# Mini_AHRS.net
KiCad netlist of a schematic drawn in Altium Designer
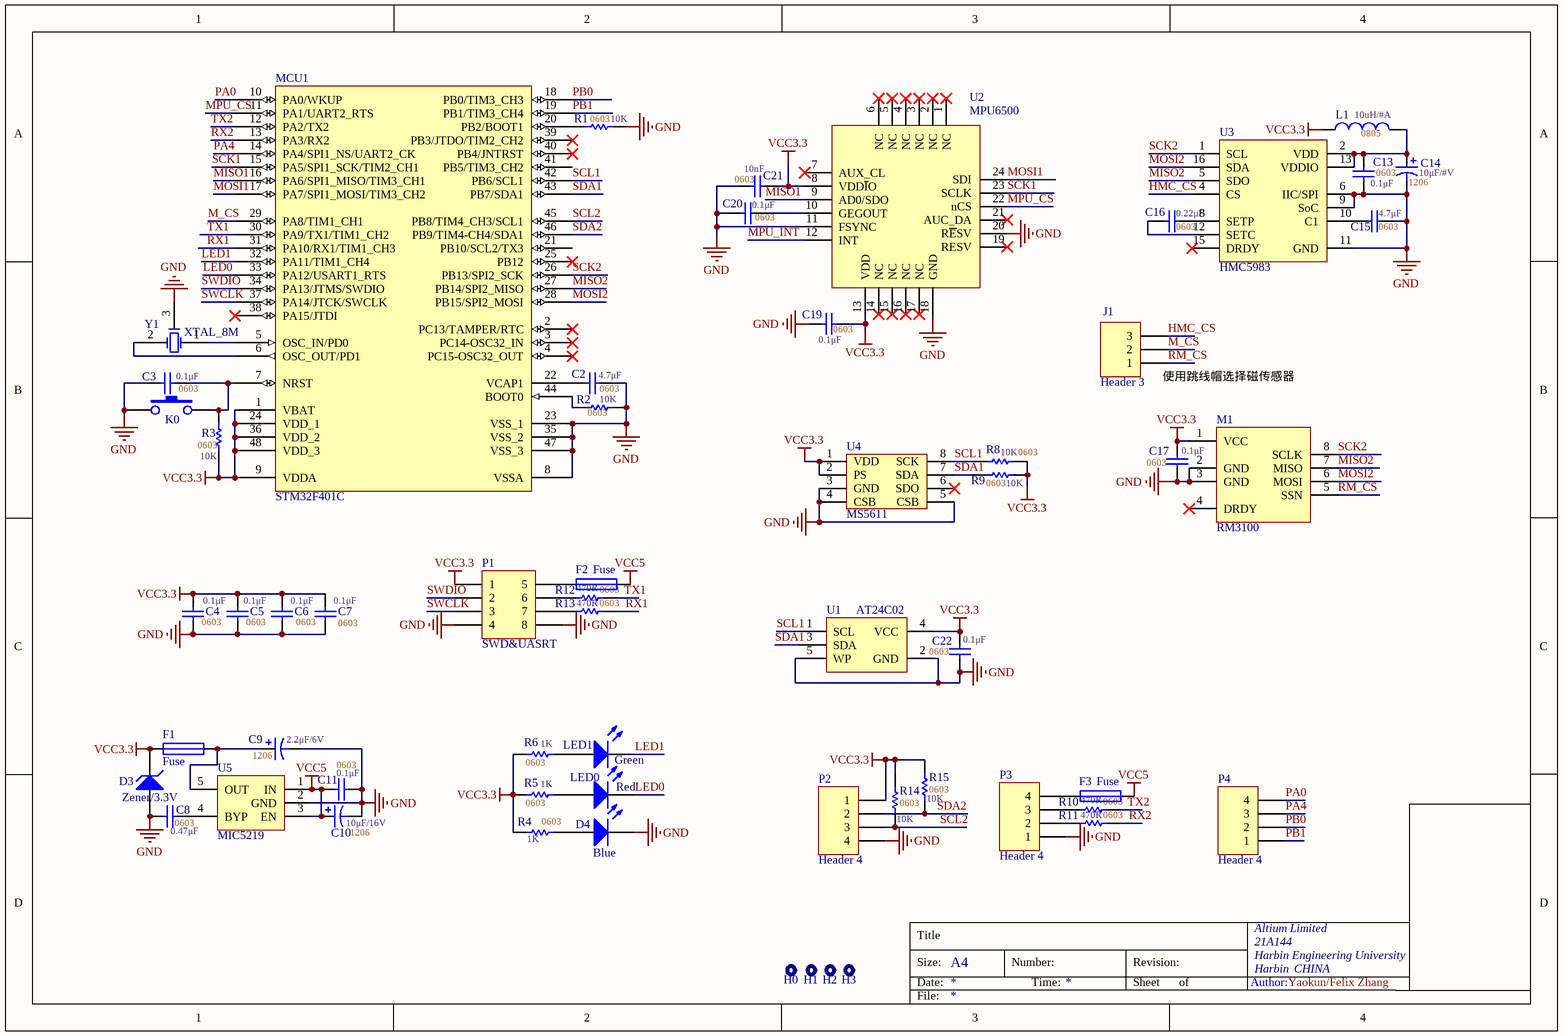
[diagram p0: Mini_AHRS.SchDoc]

(export (version "E")
  (design (tool "Eeschema 10.0.6"))
  (components
    (comp (ref "C2")
      (value "4.7μF")
      (footprint "CAP_0603_16*08")
      (description "Capacitor")
      (fields
        (field (name "PACKAGEREFERENCE") "0603")
        (field (name "Comment") "0603")
        (field (name "PUBLISHER") "Altium Limited")
      )
      (libsource (lib "Belong_to_Kongkong") (part "Cap"))
    )
    (comp (ref "C3")
      (value "0.1μF")
      (footprint "CAP_0603_16*08")
      (description "Capacitor")
      (fields
        (field (name "PACKAGEREFERENCE") "0603")
        (field (name "Comment") "0603")
        (field (name "PUBLISHER") "Altium Limited")
      )
      (libsource (lib "Belong_to_Kongkong") (part "Cap"))
    )
    (comp (ref "C4")
      (value "0.1μF")
      (footprint "CAP_0603_16*08")
      (description "Capacitor")
      (fields
        (field (name "PACKAGEREFERENCE") "0603")
        (field (name "Comment") "0603")
        (field (name "PUBLISHER") "Altium Limited")
      )
      (libsource (lib "Belong_to_Kongkong") (part "Cap"))
    )
    (comp (ref "C5")
      (value "0.1μF")
      (footprint "CAP_0603_16*08")
      (description "Capacitor")
      (fields
        (field (name "PACKAGEREFERENCE") "0603")
        (field (name "Comment") "0603")
        (field (name "PUBLISHER") "Altium Limited")
      )
      (libsource (lib "Belong_to_Kongkong") (part "Cap"))
    )
    (comp (ref "C6")
      (value "0.1μF")
      (footprint "CAP_0603_16*08")
      (description "Capacitor")
      (fields
        (field (name "PACKAGEREFERENCE") "0603")
        (field (name "Comment") "0603")
        (field (name "PUBLISHER") "Altium Limited")
      )
      (libsource (lib "Belong_to_Kongkong") (part "Cap"))
    )
    (comp (ref "C7")
      (value "0.1μF")
      (footprint "CAP_0603_16*08")
      (description "Capacitor")
      (fields
        (field (name "PACKAGEREFERENCE") "0603")
        (field (name "Comment") "0603")
        (field (name "PUBLISHER") "Altium Limited")
      )
      (libsource (lib "Belong_to_Kongkong") (part "Cap"))
    )
    (comp (ref "C8")
      (value "0.47μF")
      (footprint "CAP_0603_16*08")
      (description "Capacitor")
      (fields
        (field (name "PACKAGEREFERENCE") "0603")
        (field (name "Comment") "0603")
        (field (name "PUBLISHER") "Altium Limited")
      )
      (libsource (lib "Belong_to_Kongkong") (part "Cap"))
    )
    (comp (ref "C9")
      (value "2.2μF/6V")
      (footprint "CAP_0805_20*12")
      (description "Polarized Capacitor (Axial)")
      (fields
        (field (name "PACKAGEREFERENCE") "1206")
        (field (name "Comment") "Polar")
        (field (name "PUBLISHER") "Altium Limited")
      )
      (libsource (lib "Belong_to_Kongkong") (part "Cap Pol"))
    )
    (comp (ref "C10")
      (value "10μF/16V")
      (footprint "CAP_1206")
      (description "Polarized Capacitor (Axial)")
      (fields
        (field (name "PACKAGEREFERENCE") "1206")
        (field (name "Comment") "Polar")
        (field (name "PUBLISHER") "Altium Limited")
      )
      (libsource (lib "Belong_to_Kongkong") (part "Cap Pol"))
    )
    (comp (ref "C11")
      (value "0.1μF")
      (footprint "CAP_0603_16*08")
      (description "Capacitor")
      (fields
        (field (name "PACKAGEREFERENCE") "0603")
        (field (name "Comment") "0603")
        (field (name "PUBLISHER") "Altium Limited")
      )
      (libsource (lib "Belong_to_Kongkong") (part "Cap"))
    )
    (comp (ref "C13")
      (value "0.1μF")
      (footprint "CAP_0603_16*08")
      (description "Capacitor")
      (fields
        (field (name "PACKAGEREFERENCE") "0603")
        (field (name "Comment") "0603")
        (field (name "PUBLISHER") "Altium Limited")
      )
      (libsource (lib "Belong_to_Kongkong") (part "Cap"))
    )
    (comp (ref "C14")
      (value "10μF/#V")
      (footprint "CAP_0805_20*12")
      (description "Polarized Capacitor (Axial)")
      (fields
        (field (name "PACKAGEREFERENCE") "1206")
        (field (name "Comment") "Polar")
        (field (name "PUBLISHER") "Altium Limited")
      )
      (libsource (lib "Belong_to_Kongkong") (part "Cap Pol"))
    )
    (comp (ref "C15")
      (value "4.7μF")
      (footprint "CAP_0805_20*12")
      (description "Capacitor")
      (fields
        (field (name "PACKAGEREFERENCE") "0603")
        (field (name "Comment") "0603")
        (field (name "PUBLISHER") "Altium Limited")
      )
      (libsource (lib "Belong_to_Kongkong") (part "Cap"))
    )
    (comp (ref "C16")
      (value "0.22μF")
      (footprint "CAP_0603_16*08")
      (description "Capacitor")
      (fields
        (field (name "PACKAGEREFERENCE") "0603")
        (field (name "Comment") "0603")
        (field (name "PUBLISHER") "Altium Limited")
      )
      (libsource (lib "Belong_to_Kongkong") (part "Cap"))
    )
    (comp (ref "C17")
      (value "0.1μF")
      (footprint "CAP_0603_16*08")
      (description "Capacitor")
      (fields
        (field (name "PACKAGEREFERENCE") "0603")
        (field (name "Comment") "0603")
        (field (name "PUBLISHER") "Altium Limited")
      )
      (libsource (lib "Belong_to_Kongkong") (part "Cap"))
    )
    (comp (ref "C19")
      (value "0.1μF")
      (footprint "CAP_0603_16*08")
      (description "Capacitor")
      (fields
        (field (name "PACKAGEREFERENCE") "0603")
        (field (name "Comment") "0603")
        (field (name "PUBLISHER") "Altium Limited")
      )
      (libsource (lib "Belong_to_Kongkong") (part "Cap"))
    )
    (comp (ref "C20")
      (value "0.1μF")
      (footprint "CAP_0603_16*08")
      (description "Capacitor")
      (fields
        (field (name "PACKAGEREFERENCE") "0603")
        (field (name "Comment") "0603")
        (field (name "PUBLISHER") "Altium Limited")
      )
      (libsource (lib "Belong_to_Kongkong") (part "Cap"))
    )
    (comp (ref "C21")
      (value "10nF")
      (footprint "CAP_0603_16*08")
      (description "Capacitor")
      (fields
        (field (name "PACKAGEREFERENCE") "0603")
        (field (name "Comment") "0603")
        (field (name "PUBLISHER") "Altium Limited")
      )
      (libsource (lib "Belong_to_Kongkong") (part "Cap"))
    )
    (comp (ref "C22")
      (value "0.1μF")
      (footprint "CAP_0603_16*08")
      (description "Capacitor")
      (fields
        (field (name "PACKAGEREFERENCE") "0603")
        (field (name "Comment") "0603")
        (field (name "PUBLISHER") "Altium Limited")
      )
      (libsource (lib "Belong_to_Kongkong") (part "Cap"))
    )
    (comp (ref "D3")
      (value "Zener/3.3V")
      (footprint "SOD523")
      (description "Zener Diode")
      (fields (field (name "PUBLISHER") "Altium Limited"))
      (libsource (lib "Belong_to_Kongkong") (part "D Zener"))
    )
    (comp (ref "D4")
      (value "Blue")
      (footprint "CAP_0603_16*08")
      (description "Typical RED, GREEN, YELLOW, AMBER GaAs LED")
      (fields (field (name "PUBLISHER") "Altium Limited"))
      (libsource (lib "Belong_to_Kongkong") (part "LED"))
    )
    (comp (ref "F1")
      (value "Fuse")
      (footprint "RES_0805_20*12")
      (fields (field (name "PUBLISHER") "Altium Limited"))
      (libsource (lib "Belong_to_Kongkong") (part "Fuse 1"))
    )
    (comp (ref "F2")
      (value "Fuse")
      (footprint "RES_0805_20*12")
      (fields (field (name "PUBLISHER") "Altium Limited"))
      (libsource (lib "Belong_to_Kongkong") (part "Fuse 1"))
    )
    (comp (ref "F3")
      (value "Fuse")
      (footprint "RES_0805_20*12")
      (fields (field (name "PUBLISHER") "Altium Limited"))
      (libsource (lib "Belong_to_Kongkong") (part "Fuse 1"))
    )
    (comp (ref "H0")
      (value "Pad-SCREW")
      (footprint "PAD_M2")
      (libsource (lib "Belong_to_Kongkong") (part "Pad-SCREW"))
    )
    (comp (ref "H1")
      (value "Pad-SCREW")
      (footprint "PAD_M2")
      (libsource (lib "Belong_to_Kongkong") (part "Pad-SCREW"))
    )
    (comp (ref "H2")
      (value "Pad-SCREW")
      (footprint "PAD_M2")
      (libsource (lib "Belong_to_Kongkong") (part "Pad-SCREW"))
    )
    (comp (ref "H3")
      (value "Pad-SCREW")
      (footprint "PAD_M2")
      (libsource (lib "Belong_to_Kongkong") (part "Pad-SCREW"))
    )
    (comp (ref "J1")
      (value "Header 3")
      (footprint "HEADER1*3sig")
      (description "Header, 3-Pin")
      (fields (field (name "PUBLISHER") "Altium Limited"))
      (libsource (lib "Belong_to_Kongkong") (part "Header 3"))
    )
    (comp (ref "K0") (value "KEY") (footprint "KEY_2") (libsource (lib "Belong_to_Kongkong") (part "KEY")))
    (comp (ref "L1")
      (value "10uH/#A")
      (footprint "IND_0805_20*12")
      (description "Inductor")
      (fields
        (field (name "PACKAGEREFERENCE") "0805")
        (field (name "Comment") "MODEL?")
        (field (name "PUBLISHER") "Altium Limited")
      )
      (libsource (lib "Belong_to_Kongkong") (part "Inductor"))
    )
    (comp (ref "LED0")
      (value "Red")
      (footprint "CAP_0603_16*08")
      (description "Typical RED, GREEN, YELLOW, AMBER GaAs LED")
      (fields (field (name "PUBLISHER") "Altium Limited"))
      (libsource (lib "Belong_to_Kongkong") (part "LED"))
    )
    (comp (ref "LED1")
      (value "Green")
      (footprint "CAP_0603_16*08")
      (description "Typical RED, GREEN, YELLOW, AMBER GaAs LED")
      (fields (field (name "PUBLISHER") "Altium Limited"))
      (libsource (lib "Belong_to_Kongkong") (part "LED"))
    )
    (comp (ref "M1")
      (value "RM3100")
      (footprint "RM3100_MODEUL")
      (libsource (lib "Belong_to_Kongkong") (part "RM3100_MODEUL"))
    )
    (comp (ref "MCU1")
      (value "STM32F401C")
      (footprint "QFN-48_7x7x05P")
      (libsource (lib "Belong_to_Kongkong") (part "STM32F401C*U6"))
    )
    (comp (ref "P1")
      (value "SWD&UASRT")
      (footprint "HEADER2*4_PIN")
      (description "Header, 4-Pin, Dual row")
      (fields (field (name "PUBLISHER") "Altium Limited"))
      (libsource (lib "Belong_to_Kongkong") (part "Header 4X2"))
    )
    (comp (ref "P2")
      (value "Header 4")
      (footprint "JST_CH1.0_4P")
      (description "Header, 4-Pin")
      (fields (field (name "PUBLISHER") "Altium Limited"))
      (libsource (lib "") (part "Header 4_1"))
    )
    (comp (ref "P3")
      (value "Header 4")
      (footprint "JST_CH1.0_4P")
      (description "Header, 4-Pin")
      (fields (field (name "PUBLISHER") "Altium Limited"))
      (libsource (lib "Belong_to_Kongkong") (part "Header 4"))
    )
    (comp (ref "P4")
      (value "Header 4")
      (footprint "HEADER1*4_PIN")
      (description "Header, 4-Pin")
      (fields (field (name "PUBLISHER") "Altium Limited"))
      (libsource (lib "Belong_to_Kongkong") (part "Header 4"))
    )
    (comp (ref "R1")
      (value "10K")
      (footprint "RES_0603_16*08")
      (description "Resistor")
      (fields
        (field (name "PACKAGEREFERENCE") "0603")
        (field (name "Comment") "SMD")
        (field (name "PUBLISHER") "Altium Limited")
      )
      (libsource (lib "Belong_to_Kongkong") (part "RES_SMD"))
    )
    (comp (ref "R2")
      (value "10K")
      (footprint "RES_0603_16*08")
      (description "Resistor")
      (fields
        (field (name "PACKAGEREFERENCE") "0603")
        (field (name "Comment") "SMD")
        (field (name "PUBLISHER") "Altium Limited")
      )
      (libsource (lib "Belong_to_Kongkong") (part "RES_SMD"))
    )
    (comp (ref "R3")
      (value "10K")
      (footprint "RES_0603_16*08")
      (description "Resistor")
      (fields
        (field (name "PACKAGEREFERENCE") "0603")
        (field (name "Comment") "SMD")
        (field (name "PUBLISHER") "Altium Limited")
      )
      (libsource (lib "Belong_to_Kongkong") (part "RES_SMD"))
    )
    (comp (ref "R4")
      (value "1K")
      (footprint "RES_0603_16*08")
      (description "Resistor")
      (fields
        (field (name "PACKAGEREFERENCE") "0603")
        (field (name "Comment") "SMD")
        (field (name "PUBLISHER") "Altium Limited")
      )
      (libsource (lib "Belong_to_Kongkong") (part "RES_SMD"))
    )
    (comp (ref "R5")
      (value "1K")
      (footprint "RES_0603_16*08")
      (description "Resistor")
      (fields
        (field (name "PACKAGEREFERENCE") "0603")
        (field (name "Comment") "SMD")
        (field (name "PUBLISHER") "Altium Limited")
      )
      (libsource (lib "Belong_to_Kongkong") (part "RES_SMD"))
    )
    (comp (ref "R6")
      (value "1K")
      (footprint "RES_0603_16*08")
      (description "Resistor")
      (fields
        (field (name "PACKAGEREFERENCE") "0603")
        (field (name "Comment") "SMD")
        (field (name "PUBLISHER") "Altium Limited")
      )
      (libsource (lib "Belong_to_Kongkong") (part "RES_SMD"))
    )
    (comp (ref "R8")
      (value "10K")
      (footprint "RES_0603_16*08")
      (description "Resistor")
      (fields
        (field (name "PACKAGEREFERENCE") "0603")
        (field (name "Comment") "SMD")
        (field (name "PUBLISHER") "Altium Limited")
      )
      (libsource (lib "Belong_to_Kongkong") (part "RES_SMD"))
    )
    (comp (ref "R9")
      (value "10K")
      (footprint "RES_0603_16*08")
      (description "Resistor")
      (fields
        (field (name "PACKAGEREFERENCE") "0603")
        (field (name "Comment") "SMD")
        (field (name "PUBLISHER") "Altium Limited")
      )
      (libsource (lib "Belong_to_Kongkong") (part "RES_SMD"))
    )
    (comp (ref "R10")
      (value "470R")
      (footprint "RES_0603_16*08")
      (description "Resistor")
      (fields
        (field (name "PACKAGEREFERENCE") "0603")
        (field (name "Comment") "SMD")
        (field (name "PUBLISHER") "Altium Limited")
      )
      (libsource (lib "Belong_to_Kongkong") (part "RES_SMD"))
    )
    (comp (ref "R11")
      (value "470R")
      (footprint "RES_0603_16*08")
      (description "Resistor")
      (fields
        (field (name "PACKAGEREFERENCE") "0603")
        (field (name "Comment") "SMD")
        (field (name "PUBLISHER") "Altium Limited")
      )
      (libsource (lib "Belong_to_Kongkong") (part "RES_SMD"))
    )
    (comp (ref "R12")
      (value "470R")
      (footprint "RES_0603_16*08")
      (description "Resistor")
      (fields
        (field (name "PACKAGEREFERENCE") "0603")
        (field (name "Comment") "SMD")
        (field (name "PUBLISHER") "Altium Limited")
      )
      (libsource (lib "Belong_to_Kongkong") (part "RES_SMD"))
    )
    (comp (ref "R13")
      (value "470R")
      (footprint "RES_0603_16*08")
      (description "Resistor")
      (fields
        (field (name "PACKAGEREFERENCE") "0603")
        (field (name "Comment") "SMD")
        (field (name "PUBLISHER") "Altium Limited")
      )
      (libsource (lib "Belong_to_Kongkong") (part "RES_SMD"))
    )
    (comp (ref "R14")
      (value "10K")
      (footprint "RES_0603_16*08")
      (description "Resistor")
      (fields
        (field (name "PACKAGEREFERENCE") "0603")
        (field (name "Comment") "SMD")
        (field (name "PUBLISHER") "Altium Limited")
      )
      (libsource (lib "Belong_to_Kongkong") (part "RES_SMD"))
    )
    (comp (ref "R15")
      (value "10K")
      (footprint "RES_0603_16*08")
      (description "Resistor")
      (fields
        (field (name "PACKAGEREFERENCE") "0603")
        (field (name "Comment") "SMD")
        (field (name "PUBLISHER") "Altium Limited")
      )
      (libsource (lib "Belong_to_Kongkong") (part "RES_SMD"))
    )
    (comp (ref "U1")
      (value "AT24C02")
      (footprint "SOT23-5")
      (libsource (lib "Belong_to_Kongkong") (part "AT24C02-5Pin"))
    )
    (comp (ref "U2")
      (value "MPU6500")
      (footprint "QFN24_3*3*0.4")
      (libsource (lib "Belong_to_Kongkong") (part "MPU6500"))
    )
    (comp (ref "U3")
      (value "HMC5983")
      (footprint "QFN-16_3x3x05P")
      (libsource (lib "Belong_to_Kongkong") (part "HMC5983"))
    )
    (comp (ref "U4")
      (value "MS5611")
      (footprint "MS5611")
      (libsource (lib "Belong_to_Kongkong") (part "MS5611"))
    )
    (comp (ref "U5")
      (value "MIC5219")
      (footprint "SOT23-5")
      (libsource (lib "Belong_to_Kongkong") (part "MIC5219"))
    )
    (comp (ref "Y1")
      (value "XTAL_8M")
      (footprint "XTAL_SMD_8M")
      (libsource (lib "Belong_to_Kongkong") (part "XTAL_8M"))
    )
  )
  (nets
    (net (code "1") (name "/HMC_CS") (class "Default")
      (node (ref "J1") (pin "3") (pinfunction "3_3") (pintype "passive"))
      (node (ref "U3") (pin "4") (pinfunction "CS_4") (pintype "passive"))
    )
    (net (code "2") (name "/LED0") (class "Default")
      (node (ref "LED0") (pin "2") (pinfunction "K_2") (pintype "passive"))
      (node (ref "MCU1") (pin "33") (pinfunction "PA12/USART1_RTS_33") (pintype "bidirectional"))
    )
    (net (code "3") (name "/LED1") (class "Default")
      (node (ref "LED1") (pin "2") (pinfunction "K_2") (pintype "passive"))
      (node (ref "MCU1") (pin "32") (pinfunction "PA11/TIM1_CH4_32") (pintype "bidirectional"))
    )
    (net (code "4") (name "/MISO1") (class "Default")
      (node (ref "MCU1") (pin "16") (pinfunction "PA6/SPI1_MISO/TIM3_CH1_16") (pintype "bidirectional"))
      (node (ref "U2") (pin "9") (pinfunction "AD0/SDO_9") (pintype "open_collector"))
    )
    (net (code "5") (name "/MISO2") (class "Default")
      (node (ref "M1") (pin "7") (pinfunction "MISO_7") (pintype "power_in"))
      (node (ref "MCU1") (pin "27") (pinfunction "PB14/SPI2_MISO_27") (pintype "bidirectional"))
      (node (ref "U3") (pin "5") (pinfunction "SDO_5") (pintype "passive"))
    )
    (net (code "6") (name "/MOSI1") (class "Default")
      (node (ref "MCU1") (pin "17") (pinfunction "PA7/SPI1_MOSI/TIM3_CH2_17") (pintype "bidirectional"))
      (node (ref "U2") (pin "24") (pinfunction "SDI_24") (pintype "open_collector"))
    )
    (net (code "7") (name "/MOSI2") (class "Default")
      (node (ref "M1") (pin "6") (pinfunction "MOSI_6") (pintype "power_in"))
      (node (ref "MCU1") (pin "28") (pinfunction "PB15/SPI2_MOSI_28") (pintype "bidirectional"))
      (node (ref "U3") (pin "16") (pinfunction "SDA_16") (pintype "passive"))
    )
    (net (code "8") (name "/MPU_CS") (class "Default")
      (node (ref "MCU1") (pin "11") (pinfunction "PA1/UART2_RTS_11") (pintype "bidirectional"))
      (node (ref "U2") (pin "22") (pinfunction "nCS_22") (pintype "open_collector"))
    )
    (net (code "9") (name "/MPU_INT") (class "Default")
      (node (ref "U2") (pin "12") (pinfunction "INT_12") (pintype "open_collector"))
    )
    (net (code "10") (name "/M_CS") (class "Default")
      (node (ref "J1") (pin "2") (pinfunction "2_2") (pintype "passive"))
      (node (ref "MCU1") (pin "29") (pinfunction "PA8/TIM1_CH1_29") (pintype "bidirectional"))
    )
    (net (code "11") (name "/PA0") (class "Default")
      (node (ref "MCU1") (pin "10") (pinfunction "PA0/WKUP_10") (pintype "bidirectional"))
      (node (ref "P4") (pin "4") (pinfunction "4_4") (pintype "passive"))
    )
    (net (code "12") (name "/PA4") (class "Default")
      (node (ref "MCU1") (pin "14") (pinfunction "PA4/SPI1_NS/UART2_CK_14") (pintype "bidirectional"))
      (node (ref "P4") (pin "3") (pinfunction "3_3") (pintype "passive"))
    )
    (net (code "13") (name "/PB0") (class "Default")
      (node (ref "MCU1") (pin "18") (pinfunction "PB0/TIM3_CH3_18") (pintype "bidirectional"))
      (node (ref "P4") (pin "2") (pinfunction "2_2") (pintype "passive"))
    )
    (net (code "14") (name "/PB1") (class "Default")
      (node (ref "MCU1") (pin "19") (pinfunction "PB1/TIM3_CH4_19") (pintype "bidirectional"))
      (node (ref "P4") (pin "1") (pinfunction "1_1") (pintype "passive"))
    )
    (net (code "15") (name "/RM_CS") (class "Default")
      (node (ref "J1") (pin "1") (pinfunction "1_1") (pintype "passive"))
      (node (ref "M1") (pin "5") (pinfunction "SSN_5") (pintype "power_in"))
    )
    (net (code "16") (name "/RX1") (class "Default")
      (node (ref "MCU1") (pin "31") (pinfunction "PA10/RX1/TIM1_CH3_31") (pintype "bidirectional"))
      (node (ref "R13") (pin "1") (pinfunction "1_1") (pintype "passive"))
    )
    (net (code "17") (name "/RX2") (class "Default")
      (node (ref "MCU1") (pin "13") (pinfunction "PA3/RX2_13") (pintype "bidirectional"))
      (node (ref "R11") (pin "1") (pinfunction "1_1") (pintype "passive"))
    )
    (net (code "18") (name "/SCK1") (class "Default")
      (node (ref "MCU1") (pin "15") (pinfunction "PA5/SPI1_SCK/TIM2_CH1_15") (pintype "bidirectional"))
      (node (ref "U2") (pin "23") (pinfunction "SCLK_23") (pintype "open_collector"))
    )
    (net (code "19") (name "/SCK2") (class "Default")
      (node (ref "M1") (pin "8") (pinfunction "SCLK_8") (pintype "power_in"))
      (node (ref "MCU1") (pin "26") (pinfunction "PB13/SPI2_SCK_26") (pintype "bidirectional"))
      (node (ref "U3") (pin "1") (pinfunction "SCL_1") (pintype "passive"))
    )
    (net (code "20") (name "/SCL1") (class "Default")
      (node (ref "MCU1") (pin "42") (pinfunction "PB6/SCL1_42") (pintype "bidirectional"))
      (node (ref "R8") (pin "1") (pinfunction "1_1") (pintype "passive"))
      (node (ref "U1") (pin "1") (pinfunction "SCL_1") (pintype "passive"))
      (node (ref "U4") (pin "8") (pinfunction "SCK_8") (pintype "open_collector"))
    )
    (net (code "21") (name "/SCL2") (class "Default")
      (node (ref "MCU1") (pin "45") (pinfunction "PB8/TIM4_CH3/SCL1_45") (pintype "bidirectional"))
      (node (ref "P2") (pin "3") (pinfunction "3_3") (pintype "passive"))
      (node (ref "R14") (pin "2") (pinfunction "2_2") (pintype "passive"))
    )
    (net (code "22") (name "/SDA1") (class "Default")
      (node (ref "MCU1") (pin "43") (pinfunction "PB7/SDA1_43") (pintype "bidirectional"))
      (node (ref "R9") (pin "1") (pinfunction "1_1") (pintype "passive"))
      (node (ref "U1") (pin "3") (pinfunction "SDA_3") (pintype "passive"))
      (node (ref "U4") (pin "7") (pinfunction "SDA_7") (pintype "open_collector"))
    )
    (net (code "23") (name "/SDA2") (class "Default")
      (node (ref "MCU1") (pin "46") (pinfunction "PB9/TIM4-CH4/SDA1_46") (pintype "bidirectional"))
      (node (ref "P2") (pin "2") (pinfunction "2_2") (pintype "passive"))
      (node (ref "R15") (pin "2") (pinfunction "2_2") (pintype "passive"))
    )
    (net (code "24") (name "/SWCLK") (class "Default")
      (node (ref "MCU1") (pin "37") (pinfunction "PA14/JTCK/SWCLK_37") (pintype "bidirectional"))
      (node (ref "P1") (pin "3") (pinfunction "3_3") (pintype "passive"))
    )
    (net (code "25") (name "/SWDIO") (class "Default")
      (node (ref "MCU1") (pin "34") (pinfunction "PA13/JTMS/SWDIO_34") (pintype "bidirectional"))
      (node (ref "P1") (pin "2") (pinfunction "2_2") (pintype "passive"))
    )
    (net (code "26") (name "/TX1") (class "Default")
      (node (ref "MCU1") (pin "30") (pinfunction "PA9/TX1/TIM1_CH2_30") (pintype "bidirectional"))
      (node (ref "R12") (pin "1") (pinfunction "1_1") (pintype "passive"))
    )
    (net (code "27") (name "/TX2") (class "Default")
      (node (ref "MCU1") (pin "12") (pinfunction "PA2/TX2_12") (pintype "bidirectional"))
      (node (ref "R10") (pin "1") (pinfunction "1_1") (pintype "passive"))
    )
    (net (code "28") (name "GND") (class "Default")
      (node (ref "C10") (pin "2") (pinfunction "2_2") (pintype "passive"))
      (node (ref "C11") (pin "1") (pinfunction "1_1") (pintype "passive"))
      (node (ref "C13") (pin "2") (pinfunction "2_2") (pintype "passive"))
      (node (ref "C14") (pin "2") (pinfunction "2_2") (pintype "passive"))
      (node (ref "C15") (pin "1") (pinfunction "1_1") (pintype "passive"))
      (node (ref "C17") (pin "2") (pinfunction "2_2") (pintype "passive"))
      (node (ref "C19") (pin "2") (pinfunction "2_2") (pintype "passive"))
      (node (ref "C2") (pin "1") (pinfunction "1_1") (pintype "passive"))
      (node (ref "C20") (pin "2") (pinfunction "2_2") (pintype "passive"))
      (node (ref "C21") (pin "2") (pinfunction "2_2") (pintype "passive"))
      (node (ref "C22") (pin "2") (pinfunction "2_2") (pintype "passive"))
      (node (ref "C3") (pin "1") (pinfunction "1_1") (pintype "passive"))
      (node (ref "C4") (pin "2") (pinfunction "2_2") (pintype "passive"))
      (node (ref "C5") (pin "2") (pinfunction "2_2") (pintype "passive"))
      (node (ref "C6") (pin "2") (pinfunction "2_2") (pintype "passive"))
      (node (ref "C7") (pin "1") (pinfunction "1_1") (pintype "passive"))
      (node (ref "C8") (pin "2") (pinfunction "2_2") (pintype "passive"))
      (node (ref "C9") (pin "2") (pinfunction "2_2") (pintype "passive"))
      (node (ref "D3") (pin "1") (pinfunction "A_1") (pintype "passive"))
      (node (ref "D4") (pin "2") (pinfunction "K_2") (pintype "passive"))
      (node (ref "K0") (pin "1") (pinfunction "1_1") (pintype "passive"))
      (node (ref "M1") (pin "2") (pinfunction "GND_2") (pintype "power_in"))
      (node (ref "M1") (pin "3") (pinfunction "GND_3") (pintype "power_in"))
      (node (ref "MCU1") (pin "23") (pinfunction "VSS_1_23") (pintype "power_in"))
      (node (ref "MCU1") (pin "35") (pinfunction "VSS_2_35") (pintype "power_in"))
      (node (ref "MCU1") (pin "47") (pinfunction "VSS_3_47") (pintype "power_in"))
      (node (ref "MCU1") (pin "8") (pinfunction "VSSA_8") (pintype "power_in"))
      (node (ref "P1") (pin "4") (pinfunction "4_4") (pintype "passive"))
      (node (ref "P1") (pin "8") (pinfunction "8_8") (pintype "passive"))
      (node (ref "P2") (pin "4") (pinfunction "4_4") (pintype "passive"))
      (node (ref "P3") (pin "1") (pinfunction "1_1") (pintype "passive"))
      (node (ref "R1") (pin "2") (pinfunction "2_2") (pintype "passive"))
      (node (ref "R2") (pin "1") (pinfunction "1_1") (pintype "passive"))
      (node (ref "U1") (pin "2") (pinfunction "GND_2") (pintype "passive"))
      (node (ref "U1") (pin "5") (pinfunction "WP_5") (pintype "passive"))
      (node (ref "U2") (pin "11") (pinfunction "FSYNC_11") (pintype "open_collector"))
      (node (ref "U2") (pin "18") (pinfunction "GND_18") (pintype "open_collector"))
      (node (ref "U2") (pin "20") (pinfunction "R~{E}SV_20") (pintype "open_collector"))
      (node (ref "U3") (pin "11") (pinfunction "GND_11") (pintype "power_in"))
      (node (ref "U3") (pin "6") (pinfunction "IIC/SPI_6") (pintype "passive"))
      (node (ref "U3") (pin "9") (pinfunction "SoC_9") (pintype "passive"))
      (node (ref "U4") (pin "3") (pinfunction "GND_3") (pintype "open_collector"))
      (node (ref "U4") (pin "4") (pinfunction "CSB_4") (pintype "open_collector"))
      (node (ref "U4") (pin "5") (pinfunction "CSB_5") (pintype "open_collector"))
      (node (ref "U5") (pin "2") (pinfunction "GND_2") (pintype "passive"))
      (node (ref "Y1") (pin "3") (pinfunction "OSC3_3") (pintype "passive"))
    )
    (net (code "29") (name "Net-(D4-A)") (class "Default")
      (node (ref "D4") (pin "1") (pinfunction "A_1") (pintype "passive"))
      (node (ref "R4") (pin "2") (pinfunction "2_2") (pintype "passive"))
    )
    (net (code "30") (name "Net-(F2-Pad1)") (class "Default")
      (node (ref "F2") (pin "1") (pinfunction "1_1") (pintype "passive"))
      (node (ref "P1") (pin "5") (pinfunction "5_5") (pintype "passive"))
    )
    (net (code "31") (name "Net-(F3-Pad1)") (class "Default")
      (node (ref "F3") (pin "1") (pinfunction "1_1") (pintype "passive"))
      (node (ref "P3") (pin "4") (pinfunction "4_4") (pintype "passive"))
    )
    (net (code "32") (name "Net-(LED0-A)") (class "Default")
      (node (ref "LED0") (pin "1") (pinfunction "A_1") (pintype "passive"))
      (node (ref "R5") (pin "2") (pinfunction "2_2") (pintype "passive"))
    )
    (net (code "33") (name "Net-(LED1-A)") (class "Default")
      (node (ref "LED1") (pin "1") (pinfunction "A_1") (pintype "passive"))
      (node (ref "R6") (pin "2") (pinfunction "2_2") (pintype "passive"))
    )
    (net (code "34") (name "Net-(MCU1-BOOT0)") (class "Default")
      (node (ref "MCU1") (pin "44") (pinfunction "BOOT0_44") (pintype "input"))
      (node (ref "R2") (pin "2") (pinfunction "2_2") (pintype "passive"))
    )
    (net (code "35") (name "Net-(MCU1-NRST)") (class "Default")
      (node (ref "C3") (pin "2") (pinfunction "2_2") (pintype "passive"))
      (node (ref "K0") (pin "2") (pinfunction "2_2") (pintype "passive"))
      (node (ref "MCU1") (pin "7") (pinfunction "NRST_7") (pintype "bidirectional"))
      (node (ref "R3") (pin "1") (pinfunction "1_1") (pintype "passive"))
    )
    (net (code "36") (name "Net-(MCU1-OSC_IN{slash}PD0)") (class "Default")
      (node (ref "MCU1") (pin "5") (pinfunction "OSC_IN/PD0_5") (pintype "input"))
      (node (ref "Y1") (pin "1") (pinfunction "OSC1_1") (pintype "passive"))
    )
    (net (code "37") (name "Net-(MCU1-OSC_OUT{slash}PD1)") (class "Default")
      (node (ref "MCU1") (pin "6") (pinfunction "OSC_OUT/PD1_6") (pintype "output"))
      (node (ref "Y1") (pin "2") (pinfunction "OSC2_2") (pintype "passive"))
    )
    (net (code "38") (name "Net-(MCU1-PB2{slash}BOOT1)") (class "Default")
      (node (ref "MCU1") (pin "20") (pinfunction "PB2/BOOT1_20") (pintype "bidirectional"))
      (node (ref "R1") (pin "1") (pinfunction "1_1") (pintype "passive"))
    )
    (net (code "39") (name "Net-(MCU1-VCAP1)") (class "Default")
      (node (ref "C2") (pin "2") (pinfunction "2_2") (pintype "passive"))
      (node (ref "MCU1") (pin "22") (pinfunction "VCAP1_22") (pintype "power_in"))
    )
    (net (code "40") (name "Net-(P1-Pad6)") (class "Default")
      (node (ref "P1") (pin "6") (pinfunction "6_6") (pintype "passive"))
      (node (ref "R12") (pin "2") (pinfunction "2_2") (pintype "passive"))
    )
    (net (code "41") (name "Net-(P1-Pad7)") (class "Default")
      (node (ref "P1") (pin "7") (pinfunction "7_7") (pintype "passive"))
      (node (ref "R13") (pin "2") (pinfunction "2_2") (pintype "passive"))
    )
    (net (code "42") (name "Net-(P3-Pad2)") (class "Default")
      (node (ref "P3") (pin "2") (pinfunction "2_2") (pintype "passive"))
      (node (ref "R11") (pin "2") (pinfunction "2_2") (pintype "passive"))
    )
    (net (code "43") (name "Net-(P3-Pad3)") (class "Default")
      (node (ref "P3") (pin "3") (pinfunction "3_3") (pintype "passive"))
      (node (ref "R10") (pin "2") (pinfunction "2_2") (pintype "passive"))
    )
    (net (code "44") (name "Net-(U2-GEGOUT)") (class "Default")
      (node (ref "C20") (pin "1") (pinfunction "1_1") (pintype "passive"))
      (node (ref "U2") (pin "10") (pinfunction "GEGOUT_10") (pintype "open_collector"))
    )
    (net (code "45") (name "Net-(U3-C1)") (class "Default")
      (node (ref "C15") (pin "2") (pinfunction "2_2") (pintype "passive"))
      (node (ref "U3") (pin "10") (pinfunction "C1_10") (pintype "passive"))
    )
    (net (code "46") (name "Net-(U3-SETC)") (class "Default")
      (node (ref "C16") (pin "2") (pinfunction "2_2") (pintype "passive"))
      (node (ref "U3") (pin "12") (pinfunction "SETC_12") (pintype "passive"))
    )
    (net (code "47") (name "Net-(U3-SETP)") (class "Default")
      (node (ref "C16") (pin "1") (pinfunction "1_1") (pintype "passive"))
      (node (ref "U3") (pin "8") (pinfunction "SETP_8") (pintype "passive"))
    )
    (net (code "48") (name "Net-(U3-VDD)") (class "Default")
      (node (ref "C13") (pin "1") (pinfunction "1_1") (pintype "passive"))
      (node (ref "C14") (pin "1") (pinfunction "1_1") (pintype "passive"))
      (node (ref "L1") (pin "2") (pinfunction "2_2") (pintype "passive"))
      (node (ref "U3") (pin "13") (pinfunction "VDDIO_13") (pintype "passive"))
      (node (ref "U3") (pin "2") (pinfunction "VDD_2") (pintype "power_in"))
    )
    (net (code "49") (name "Net-(U5-BYP)") (class "Default")
      (node (ref "C8") (pin "1") (pinfunction "1_1") (pintype "passive"))
      (node (ref "U5") (pin "4") (pinfunction "BYP_4") (pintype "passive"))
    )
    (net (code "50") (name "Net-(U5-OUT)") (class "Default")
      (node (ref "C9") (pin "1") (pinfunction "1_1") (pintype "passive"))
      (node (ref "F1") (pin "2") (pinfunction "2_2") (pintype "passive"))
      (node (ref "U5") (pin "5") (pinfunction "OUT_5") (pintype "passive"))
    )
    (net (code "51") (name "VCC3.3") (class "Default")
      (node (ref "C17") (pin "1") (pinfunction "1_1") (pintype "passive"))
      (node (ref "C19") (pin "1") (pinfunction "1_1") (pintype "passive"))
      (node (ref "C21") (pin "1") (pinfunction "1_1") (pintype "passive"))
      (node (ref "C22") (pin "1") (pinfunction "1_1") (pintype "passive"))
      (node (ref "C4") (pin "1") (pinfunction "1_1") (pintype "passive"))
      (node (ref "C5") (pin "1") (pinfunction "1_1") (pintype "passive"))
      (node (ref "C6") (pin "1") (pinfunction "1_1") (pintype "passive"))
      (node (ref "C7") (pin "2") (pinfunction "2_2") (pintype "passive"))
      (node (ref "D3") (pin "2") (pinfunction "K_2") (pintype "passive"))
      (node (ref "F1") (pin "1") (pinfunction "1_1") (pintype "passive"))
      (node (ref "L1") (pin "1") (pinfunction "1_1") (pintype "passive"))
      (node (ref "M1") (pin "1") (pinfunction "VCC_1") (pintype "power_in"))
      (node (ref "MCU1") (pin "1") (pinfunction "VBAT_1") (pintype "power_in"))
      (node (ref "MCU1") (pin "24") (pinfunction "VDD_1_24") (pintype "power_in"))
      (node (ref "MCU1") (pin "36") (pinfunction "VDD_2_36") (pintype "power_in"))
      (node (ref "MCU1") (pin "48") (pinfunction "VDD_3_48") (pintype "power_in"))
      (node (ref "MCU1") (pin "9") (pinfunction "VDDA_9") (pintype "power_in"))
      (node (ref "P1") (pin "1") (pinfunction "1_1") (pintype "passive"))
      (node (ref "P2") (pin "1") (pinfunction "1_1") (pintype "passive"))
      (node (ref "R14") (pin "1") (pinfunction "1_1") (pintype "passive"))
      (node (ref "R15") (pin "1") (pinfunction "1_1") (pintype "passive"))
      (node (ref "R3") (pin "2") (pinfunction "2_2") (pintype "passive"))
      (node (ref "R4") (pin "1") (pinfunction "1_1") (pintype "passive"))
      (node (ref "R5") (pin "1") (pinfunction "1_1") (pintype "passive"))
      (node (ref "R6") (pin "1") (pinfunction "1_1") (pintype "passive"))
      (node (ref "R8") (pin "2") (pinfunction "2_2") (pintype "passive"))
      (node (ref "R9") (pin "2") (pinfunction "2_2") (pintype "passive"))
      (node (ref "U1") (pin "4") (pinfunction "VCC_4") (pintype "passive"))
      (node (ref "U2") (pin "13") (pinfunction "VDD_13") (pintype "open_collector"))
      (node (ref "U2") (pin "8") (pinfunction "VDD~{I}O_8") (pintype "open_collector"))
      (node (ref "U4") (pin "1") (pinfunction "VDD_1") (pintype "open_collector"))
      (node (ref "U4") (pin "2") (pinfunction "PS_2") (pintype "open_collector"))
    )
    (net (code "52") (name "VCC5") (class "Default")
      (node (ref "C10") (pin "1") (pinfunction "1_1") (pintype "passive"))
      (node (ref "C11") (pin "2") (pinfunction "2_2") (pintype "passive"))
      (node (ref "F2") (pin "2") (pinfunction "2_2") (pintype "passive"))
      (node (ref "F3") (pin "2") (pinfunction "2_2") (pintype "passive"))
      (node (ref "U5") (pin "1") (pinfunction "IN_1") (pintype "passive"))
      (node (ref "U5") (pin "3") (pinfunction "EN_3") (pintype "passive"))
    )
    (net (code "53") (name "unconnected-(M1-DRDY-Pad4)") (class "Default")
      (node (ref "M1") (pin "4") (pinfunction "DRDY_4") (pintype "passive+no_connect"))
    )
    (net (code "54") (name "unconnected-(MCU1-PA15{slash}JTDI-Pad38)") (class "Default")
      (node (ref "MCU1") (pin "38") (pinfunction "PA15/JTDI_38") (pintype "bidirectional+no_connect"))
    )
    (net (code "55") (name "unconnected-(MCU1-PB3{slash}JTDO{slash}TIM2_CH2-Pad39)") (class "Default")
      (node (ref "MCU1") (pin "39") (pinfunction "PB3/JTDO/TIM2_CH2_39") (pintype "bidirectional+no_connect"))
    )
    (net (code "56") (name "unconnected-(MCU1-PB4{slash}JNTRST-Pad40)") (class "Default")
      (node (ref "MCU1") (pin "40") (pinfunction "PB4/JNTRST_40") (pintype "bidirectional+no_connect"))
    )
    (net (code "57") (name "unconnected-(MCU1-PB5{slash}TIM3_CH2-Pad41)") (class "Default")
      (node (ref "MCU1") (pin "41") (pinfunction "PB5/TIM3_CH2_41") (pintype "bidirectional"))
    )
    (net (code "58") (name "unconnected-(MCU1-PB10{slash}SCL2{slash}TX3-Pad21)") (class "Default")
      (node (ref "MCU1") (pin "21") (pinfunction "PB10/SCL2/TX3_21") (pintype "bidirectional"))
    )
    (net (code "59") (name "unconnected-(MCU1-PB12-Pad25)") (class "Default")
      (node (ref "MCU1") (pin "25") (pinfunction "PB12_25") (pintype "bidirectional+no_connect"))
    )
    (net (code "60") (name "unconnected-(MCU1-PC13{slash}TAMPER{slash}RTC-Pad2)") (class "Default")
      (node (ref "MCU1") (pin "2") (pinfunction "PC13/TAMPER/RTC_2") (pintype "bidirectional+no_connect"))
    )
    (net (code "61") (name "unconnected-(MCU1-PC14-OSC32_IN-Pad3)") (class "Default")
      (node (ref "MCU1") (pin "3") (pinfunction "PC14-OSC32_IN_3") (pintype "bidirectional+no_connect"))
    )
    (net (code "62") (name "unconnected-(MCU1-PC15-OSC32_OUT-Pad4)") (class "Default")
      (node (ref "MCU1") (pin "4") (pinfunction "PC15-OSC32_OUT_4") (pintype "bidirectional+no_connect"))
    )
    (net (code "63") (name "unconnected-(U2-AUC_DA-Pad21)") (class "Default")
      (node (ref "U2") (pin "21") (pinfunction "AUC_DA_21") (pintype "open_collector+no_connect"))
    )
    (net (code "64") (name "unconnected-(U2-AUX_CL-Pad7)") (class "Default")
      (node (ref "U2") (pin "7") (pinfunction "AUX_CL_7") (pintype "open_collector+no_connect"))
    )
    (net (code "65") (name "unconnected-(U2-NC-Pad1)") (class "Default")
      (node (ref "U2") (pin "1") (pinfunction "NC_1") (pintype "open_collector+no_connect"))
    )
    (net (code "66") (name "unconnected-(U2-NC-Pad2)") (class "Default")
      (node (ref "U2") (pin "2") (pinfunction "NC_2") (pintype "open_collector+no_connect"))
    )
    (net (code "67") (name "unconnected-(U2-NC-Pad3)") (class "Default")
      (node (ref "U2") (pin "3") (pinfunction "NC_3") (pintype "open_collector+no_connect"))
    )
    (net (code "68") (name "unconnected-(U2-NC-Pad4)") (class "Default")
      (node (ref "U2") (pin "4") (pinfunction "NC_4") (pintype "open_collector+no_connect"))
    )
    (net (code "69") (name "unconnected-(U2-NC-Pad5)") (class "Default")
      (node (ref "U2") (pin "5") (pinfunction "NC_5") (pintype "open_collector+no_connect"))
    )
    (net (code "70") (name "unconnected-(U2-NC-Pad6)") (class "Default")
      (node (ref "U2") (pin "6") (pinfunction "NC_6") (pintype "open_collector+no_connect"))
    )
    (net (code "71") (name "unconnected-(U2-NC-Pad14)") (class "Default")
      (node (ref "U2") (pin "14") (pinfunction "NC_14") (pintype "open_collector+no_connect"))
    )
    (net (code "72") (name "unconnected-(U2-NC-Pad15)") (class "Default")
      (node (ref "U2") (pin "15") (pinfunction "NC_15") (pintype "open_collector+no_connect"))
    )
    (net (code "73") (name "unconnected-(U2-NC-Pad16)") (class "Default")
      (node (ref "U2") (pin "16") (pinfunction "NC_16") (pintype "open_collector+no_connect"))
    )
    (net (code "74") (name "unconnected-(U2-NC-Pad17)") (class "Default")
      (node (ref "U2") (pin "17") (pinfunction "NC_17") (pintype "open_collector+no_connect"))
    )
    (net (code "75") (name "unconnected-(U2-RESV-Pad19)") (class "Default")
      (node (ref "U2") (pin "19") (pinfunction "RESV_19") (pintype "open_collector+no_connect"))
    )
    (net (code "76") (name "unconnected-(U3-DRDY-Pad15)") (class "Default")
      (node (ref "U3") (pin "15") (pinfunction "DRDY_15") (pintype "passive+no_connect"))
    )
    (net (code "77") (name "unconnected-(U4-SDO-Pad6)") (class "Default")
      (node (ref "U4") (pin "6") (pinfunction "SDO_6") (pintype "open_collector+no_connect"))
    )
  )
)
